# HV_power.net
KiCad netlist of a schematic drawn in Altium Designer
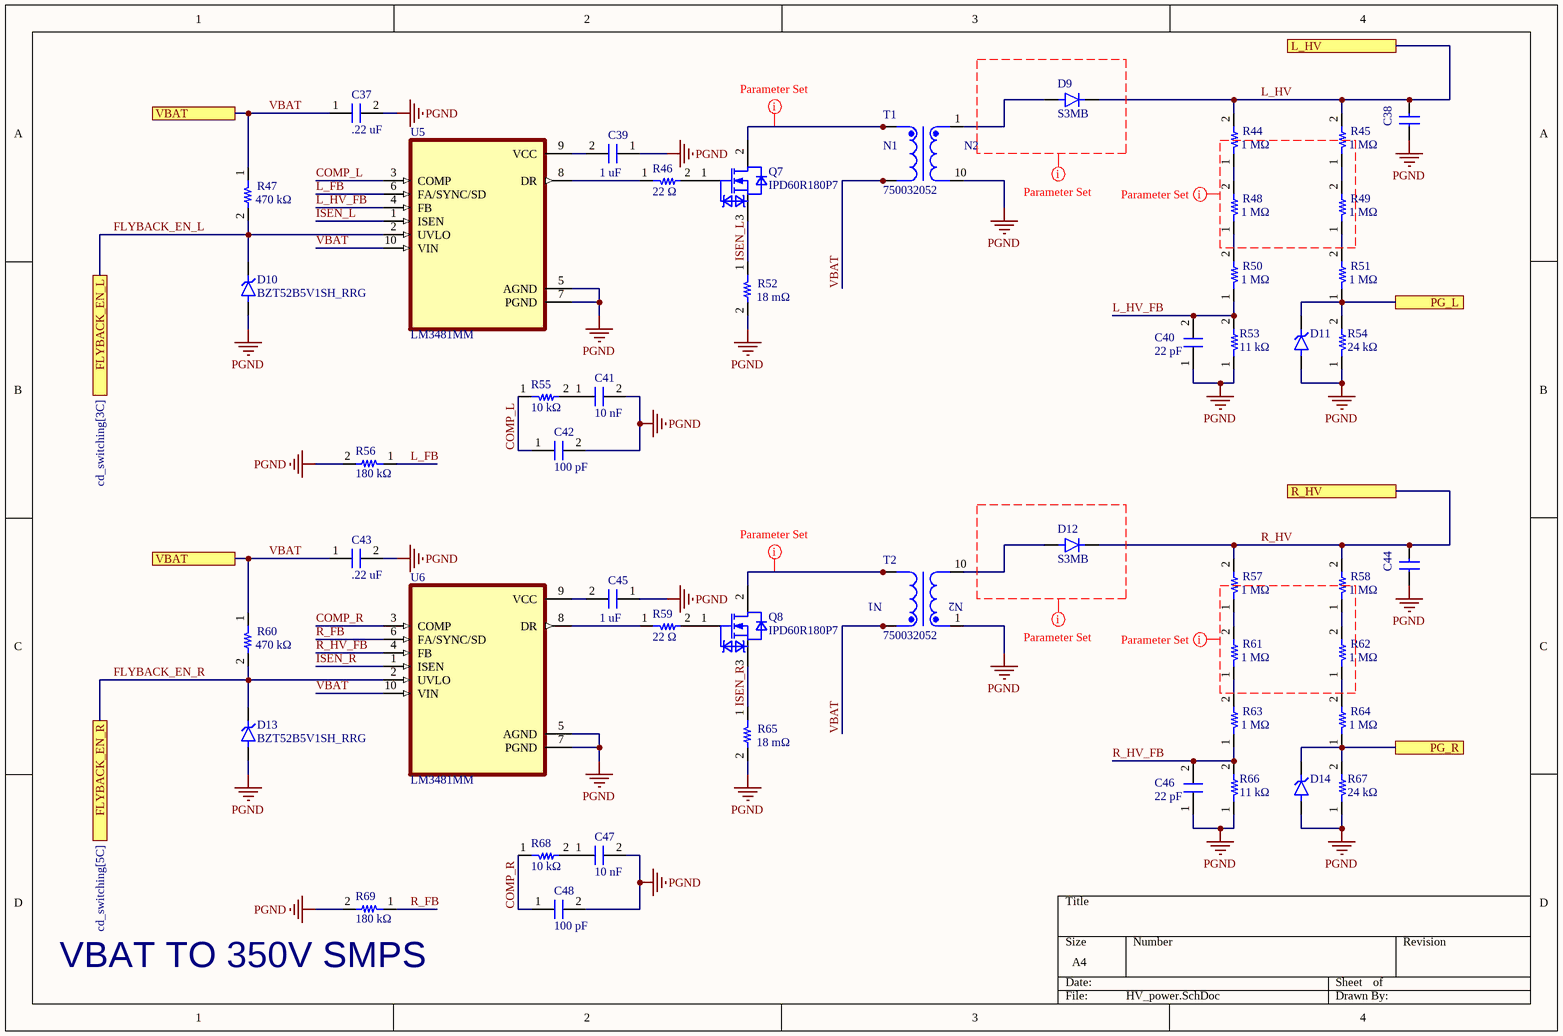
[diagram p0: HV_power.SchDoc]

(export (version "E")
  (design (tool "Eeschema 10.0.6"))
  (components
    (comp (ref "C37")
      (value ".22 uF")
      (footprint "0603_FP")
      (fields (field (name "Comment") "GRM21BR61C475KA88L"))
      (libsource (lib "RC_sch") (part "Capacitor_0603"))
    )
    (comp (ref "C38")
      (value "WCAP-FTBP_P10")
      (footprint "WCAP-FTBP_10X13X5.5X11(PXLXWXH)")
      (fields (field (name "MF") "Wurth Elektronik") (field (name "MP") "890283323005CS"))
      (libsource (lib "WCAP-FTBP_P10") (part "WCAP-FTBP_P10"))
    )
    (comp (ref "C39")
      (value "1 uF")
      (footprint "0603_FP")
      (fields (field (name "Comment") "Capacitor_0603"))
      (libsource (lib "RC_sch") (part "Capacitor_0603"))
    )
    (comp (ref "C40")
      (value "22 pF")
      (footprint "0603_FP")
      (fields (field (name "Comment") "Capacitor_0603"))
      (libsource (lib "RC_sch") (part "Capacitor_0603"))
    )
    (comp (ref "C41")
      (value "10 nF")
      (footprint "0603_FP")
      (fields (field (name "Comment") "Capacitor_0603"))
      (libsource (lib "RC_sch") (part "Capacitor_0603"))
    )
    (comp (ref "C42")
      (value "100 pF")
      (footprint "0603_FP")
      (fields (field (name "Comment") "Capacitor_0603"))
      (libsource (lib "RC_sch") (part "Capacitor_0603"))
    )
    (comp (ref "C43")
      (value ".22 uF")
      (footprint "0603_FP")
      (fields (field (name "Comment") "GRM21BR61C475KA88L"))
      (libsource (lib "RC_sch") (part "Capacitor_0603"))
    )
    (comp (ref "C44")
      (value "WCAP-FTBP_P10")
      (footprint "WCAP-FTBP_10X13X5.5X11(PXLXWXH)")
      (fields (field (name "MF") "Wurth Elektronik") (field (name "MP") "890283323005CS"))
      (libsource (lib "WCAP-FTBP_P10") (part "WCAP-FTBP_P10"))
    )
    (comp (ref "C45")
      (value "1 uF")
      (footprint "0603_FP")
      (fields (field (name "Comment") "Capacitor_0603"))
      (libsource (lib "RC_sch") (part "Capacitor_0603"))
    )
    (comp (ref "C46")
      (value "22 pF")
      (footprint "0603_FP")
      (fields (field (name "Comment") "Capacitor_0603"))
      (libsource (lib "RC_sch") (part "Capacitor_0603"))
    )
    (comp (ref "C47")
      (value "10 nF")
      (footprint "0603_FP")
      (fields (field (name "Comment") "Capacitor_0603"))
      (libsource (lib "RC_sch") (part "Capacitor_0603"))
    )
    (comp (ref "C48")
      (value "100 pF")
      (footprint "0603_FP")
      (fields (field (name "Comment") "Capacitor_0603"))
      (libsource (lib "RC_sch") (part "Capacitor_0603"))
    )
    (comp (ref "D9")
      (value "S3MB")
      (footprint "DIOM4336X265N")
      (description "3A, 1000V, Standard Recovery Rectifier")
      (fields (field (name "MF") "Taiwan Semiconductor"))
      (libsource (lib "S3MB") (part "S3MB"))
    )
    (comp (ref "D10")
      (value "BZT52B5V1SH_RRG")
      (footprint "DIO_BZT52B5V1SH_RRG")
      (description "SOD-323, 200mW, 2%, 5.1V, Zener Diode")
      (fields (field (name "MF") "Taiwan Semiconductor Corporation") (field (name "MP") "BZT52B5V1SH RRG"))
      (libsource (lib "BZT52B5V1SH_RRG") (part "BZT52B5V1SH_RRG"))
    )
    (comp (ref "D11")
      (value "BZT52B15SH_RRG")
      (footprint "DIO_BZT52B15SH_RRG")
      (description "SOD-323, 200mW, 2%, 15V, Zener Diode")
      (fields (field (name "MF") "Taiwan Semiconductor Corporation") (field (name "MP") "BZT52B15SH RRG"))
      (libsource (lib "BZT52B15SH_RRG") (part "BZT52B15SH_RRG"))
    )
    (comp (ref "D12")
      (value "S3MB")
      (footprint "DIOM4336X265N")
      (description "3A, 1000V, Standard Recovery Rectifier")
      (fields (field (name "MF") "Taiwan Semiconductor"))
      (libsource (lib "S3MB") (part "S3MB"))
    )
    (comp (ref "D13")
      (value "BZT52B5V1SH_RRG")
      (footprint "DIO_BZT52B5V1SH_RRG")
      (description "SOD-323, 200mW, 2%, 5.1V, Zener Diode")
      (fields (field (name "MF") "Taiwan Semiconductor Corporation") (field (name "MP") "BZT52B5V1SH RRG"))
      (libsource (lib "BZT52B5V1SH_RRG") (part "BZT52B5V1SH_RRG"))
    )
    (comp (ref "D14")
      (value "BZT52B15SH_RRG")
      (footprint "DIO_BZT52B15SH_RRG")
      (description "SOD-323, 200mW, 2%, 15V, Zener Diode")
      (fields (field (name "MF") "Taiwan Semiconductor Corporation") (field (name "MP") "BZT52B15SH RRG"))
      (libsource (lib "BZT52B15SH_RRG") (part "BZT52B15SH_RRG"))
    )
    (comp (ref "Q7")
      (value "IPD60R180P7")
      (footprint "DPAK228P987X240-3N")
      (fields (field (name "MANUFACTURER") "Infineon Technologies"))
      (libsource (lib "IPD60R180P7") (part "IPD60R180P7"))
    )
    (comp (ref "Q8")
      (value "IPD60R180P7")
      (footprint "DPAK228P987X240-3N")
      (fields (field (name "MANUFACTURER") "Infineon Technologies"))
      (libsource (lib "IPD60R180P7") (part "IPD60R180P7"))
    )
    (comp (ref "R44")
      (value "1 MΩ")
      (footprint "0805_FP")
      (fields (field (name "Comment") "R_0805"))
      (libsource (lib "0805_R") (part "R_0805"))
    )
    (comp (ref "R45")
      (value "1 MΩ")
      (footprint "0805_FP")
      (fields (field (name "Comment") "R_0805"))
      (libsource (lib "0805_R") (part "R_0805"))
    )
    (comp (ref "R46")
      (value "22 Ω")
      (footprint "0603_FP")
      (fields (field (name "Comment") "Resistor_0603"))
      (libsource (lib "RC_sch") (part "Resistor_0603"))
    )
    (comp (ref "R47")
      (value "470 kΩ")
      (footprint "0603_FP")
      (fields (field (name "Comment") "Resistor_0603"))
      (libsource (lib "RC_sch") (part "Resistor_0603"))
    )
    (comp (ref "R48")
      (value "1 MΩ")
      (footprint "0805_FP")
      (fields (field (name "Comment") "R_0805"))
      (libsource (lib "0805_R") (part "R_0805"))
    )
    (comp (ref "R49")
      (value "1 MΩ")
      (footprint "0805_FP")
      (fields (field (name "Comment") "R_0805"))
      (libsource (lib "0805_R") (part "R_0805"))
    )
    (comp (ref "R50")
      (value "1 MΩ")
      (footprint "0805_FP")
      (fields (field (name "Comment") "R_0805"))
      (libsource (lib "0805_R") (part "R_0805"))
    )
    (comp (ref "R51")
      (value "1 MΩ")
      (footprint "0805_FP")
      (fields (field (name "Comment") "R_0805"))
      (libsource (lib "0805_R") (part "R_0805"))
    )
    (comp (ref "R52")
      (value "18 mΩ")
      (footprint "2010_FP")
      (fields (field (name "Comment") "2010_res"))
      (libsource (lib "2010_R") (part "2010_res"))
    )
    (comp (ref "R53")
      (value "11 kΩ")
      (footprint "0805_FP")
      (fields (field (name "Comment") "R_0805"))
      (libsource (lib "0805_R") (part "R_0805"))
    )
    (comp (ref "R54")
      (value "24 kΩ")
      (footprint "0805_FP")
      (fields (field (name "Comment") "R_0805"))
      (libsource (lib "0805_R") (part "R_0805"))
    )
    (comp (ref "R55")
      (value "10 kΩ")
      (footprint "0603_FP")
      (fields (field (name "Comment") "Resistor_0603"))
      (libsource (lib "RC_sch") (part "Resistor_0603"))
    )
    (comp (ref "R56")
      (value "180 kΩ")
      (footprint "0603_FP")
      (fields (field (name "Comment") "Resistor_0603"))
      (libsource (lib "RC_sch") (part "Resistor_0603"))
    )
    (comp (ref "R57")
      (value "1 MΩ")
      (footprint "0805_FP")
      (fields (field (name "Comment") "R_0805"))
      (libsource (lib "0805_R") (part "R_0805"))
    )
    (comp (ref "R58")
      (value "1 MΩ")
      (footprint "0805_FP")
      (fields (field (name "Comment") "R_0805"))
      (libsource (lib "0805_R") (part "R_0805"))
    )
    (comp (ref "R59")
      (value "22 Ω")
      (footprint "0603_FP")
      (fields (field (name "Comment") "Resistor_0603"))
      (libsource (lib "RC_sch") (part "Resistor_0603"))
    )
    (comp (ref "R60")
      (value "470 kΩ")
      (footprint "0603_FP")
      (fields (field (name "Comment") "Resistor_0603"))
      (libsource (lib "RC_sch") (part "Resistor_0603"))
    )
    (comp (ref "R61")
      (value "1 MΩ")
      (footprint "0805_FP")
      (fields (field (name "Comment") "R_0805"))
      (libsource (lib "0805_R") (part "R_0805"))
    )
    (comp (ref "R62")
      (value "1 MΩ")
      (footprint "0805_FP")
      (fields (field (name "Comment") "R_0805"))
      (libsource (lib "0805_R") (part "R_0805"))
    )
    (comp (ref "R63")
      (value "1 MΩ")
      (footprint "0805_FP")
      (fields (field (name "Comment") "R_0805"))
      (libsource (lib "0805_R") (part "R_0805"))
    )
    (comp (ref "R64")
      (value "1 MΩ")
      (footprint "0805_FP")
      (fields (field (name "Comment") "R_0805"))
      (libsource (lib "0805_R") (part "R_0805"))
    )
    (comp (ref "R65")
      (value "18 mΩ")
      (footprint "2010_FP")
      (fields (field (name "Comment") "2010_res"))
      (libsource (lib "2010_R") (part "2010_res"))
    )
    (comp (ref "R66")
      (value "11 kΩ")
      (footprint "0805_FP")
      (fields (field (name "Comment") "R_0805"))
      (libsource (lib "0805_R") (part "R_0805"))
    )
    (comp (ref "R67")
      (value "24 kΩ")
      (footprint "0805_FP")
      (fields (field (name "Comment") "R_0805"))
      (libsource (lib "0805_R") (part "R_0805"))
    )
    (comp (ref "R68")
      (value "10 kΩ")
      (footprint "0603_FP")
      (fields (field (name "Comment") "Resistor_0603"))
      (libsource (lib "RC_sch") (part "Resistor_0603"))
    )
    (comp (ref "R69")
      (value "180 kΩ")
      (footprint "0603_FP")
      (fields (field (name "Comment") "Resistor_0603"))
      (libsource (lib "RC_sch") (part "Resistor_0603"))
    )
    (comp (ref "T1")
      (value "750032052")
      (footprint "WE-FB3751_EFD20")
      (fields (field (name "MF") "Wurth Electronics"))
      (libsource (lib "750032052") (part "750032052"))
    )
    (comp (ref "T2")
      (value "750032052")
      (footprint "WE-FB3751_EFD20")
      (fields (field (name "MF") "Wurth Electronics"))
      (libsource (lib "") (part "750032052_1"))
    )
    (comp (ref "U5")
      (value "LM3481MM")
      (footprint "SOP50P490X110-10N")
      (description "2.97V to 48V High-Efficiency Controller for Boost, SEPIC and Flyback")
      (fields (field (name "MF") "Texas Instruments") (field (name "MP") "LM3481MM/NOPB"))
      (libsource (lib "LM3481MM") (part "LM3481MM"))
    )
    (comp (ref "U6")
      (value "LM3481MM")
      (footprint "SOP50P490X110-10N")
      (description "2.97V to 48V High-Efficiency Controller for Boost, SEPIC and Flyback")
      (fields (field (name "MF") "Texas Instruments") (field (name "MP") "LM3481MM/NOPB"))
      (libsource (lib "LM3481MM") (part "LM3481MM"))
    )
  )
  (nets
    (net (code "1") (name "/COMP_L") (class "Default")
      (node (ref "C42") (pin "1") (pinfunction "1_1") (pintype "passive"))
      (node (ref "R55") (pin "1") (pinfunction "1_1") (pintype "passive"))
      (node (ref "U5") (pin "3") (pinfunction "COMP_3") (pintype "input"))
    )
    (net (code "2") (name "/COMP_R") (class "Default")
      (node (ref "C48") (pin "1") (pinfunction "1_1") (pintype "passive"))
      (node (ref "R68") (pin "1") (pinfunction "1_1") (pintype "passive"))
      (node (ref "U6") (pin "3") (pinfunction "COMP_3") (pintype "input"))
    )
    (net (code "3") (name "/FLYBACK_EN_L") (class "Default")
      (node (ref "D10") (pin "1") (pinfunction "K_1") (pintype "passive"))
      (node (ref "R47") (pin "2") (pinfunction "2_2") (pintype "passive"))
      (node (ref "U5") (pin "2") (pinfunction "UVLO_2") (pintype "input"))
    )
    (net (code "4") (name "/FLYBACK_EN_R") (class "Default")
      (node (ref "D13") (pin "1") (pinfunction "K_1") (pintype "passive"))
      (node (ref "R60") (pin "2") (pinfunction "2_2") (pintype "passive"))
      (node (ref "U6") (pin "2") (pinfunction "UVLO_2") (pintype "input"))
    )
    (net (code "5") (name "/ISEN_L") (class "Default")
      (node (ref "Q7") (pin "3") (pinfunction "SOURCE_3") (pintype "passive"))
      (node (ref "R52") (pin "1") (pinfunction "1_1") (pintype "passive"))
      (node (ref "U5") (pin "1") (pinfunction "ISEN_1") (pintype "input"))
    )
    (net (code "6") (name "/ISEN_R") (class "Default")
      (node (ref "Q8") (pin "3") (pinfunction "SOURCE_3") (pintype "passive"))
      (node (ref "R65") (pin "1") (pinfunction "1_1") (pintype "passive"))
      (node (ref "U6") (pin "1") (pinfunction "ISEN_1") (pintype "input"))
    )
    (net (code "7") (name "/L_FB") (class "Default")
      (node (ref "R56") (pin "1") (pinfunction "1_1") (pintype "passive"))
      (node (ref "U5") (pin "6") (pinfunction "FA/SYNC/SD_6") (pintype "input"))
    )
    (net (code "8") (name "/L_HV") (class "Default")
      (node (ref "C38") (pin "2") (pinfunction "2_2") (pintype "passive"))
      (node (ref "D9") (pin "C") (pinfunction "K_C") (pintype "passive"))
      (node (ref "R44") (pin "2") (pinfunction "2_2") (pintype "passive"))
      (node (ref "R45") (pin "2") (pinfunction "2_2") (pintype "passive"))
    )
    (net (code "9") (name "/L_HV_FB") (class "Default")
      (node (ref "C40") (pin "2") (pinfunction "2_2") (pintype "passive"))
      (node (ref "R50") (pin "1") (pinfunction "1_1") (pintype "passive"))
      (node (ref "R53") (pin "2") (pinfunction "2_2") (pintype "passive"))
      (node (ref "U5") (pin "4") (pinfunction "FB_4") (pintype "input"))
    )
    (net (code "10") (name "/PG_L") (class "Default")
      (node (ref "D11") (pin "1") (pinfunction "K_1") (pintype "passive"))
      (node (ref "R51") (pin "1") (pinfunction "1_1") (pintype "passive"))
      (node (ref "R54") (pin "2") (pinfunction "2_2") (pintype "passive"))
    )
    (net (code "11") (name "/PG_R") (class "Default")
      (node (ref "D14") (pin "1") (pinfunction "K_1") (pintype "passive"))
      (node (ref "R64") (pin "1") (pinfunction "1_1") (pintype "passive"))
      (node (ref "R67") (pin "2") (pinfunction "2_2") (pintype "passive"))
    )
    (net (code "12") (name "/R_FB") (class "Default")
      (node (ref "R69") (pin "1") (pinfunction "1_1") (pintype "passive"))
      (node (ref "U6") (pin "6") (pinfunction "FA/SYNC/SD_6") (pintype "input"))
    )
    (net (code "13") (name "/R_HV") (class "Default")
      (node (ref "C44") (pin "2") (pinfunction "2_2") (pintype "passive"))
      (node (ref "D12") (pin "C") (pinfunction "K_C") (pintype "passive"))
      (node (ref "R57") (pin "2") (pinfunction "2_2") (pintype "passive"))
      (node (ref "R58") (pin "2") (pinfunction "2_2") (pintype "passive"))
    )
    (net (code "14") (name "/R_HV_FB") (class "Default")
      (node (ref "C46") (pin "2") (pinfunction "2_2") (pintype "passive"))
      (node (ref "R63") (pin "1") (pinfunction "1_1") (pintype "passive"))
      (node (ref "R66") (pin "2") (pinfunction "2_2") (pintype "passive"))
      (node (ref "U6") (pin "4") (pinfunction "FB_4") (pintype "input"))
    )
    (net (code "15") (name "/VBAT") (class "Default")
      (node (ref "C37") (pin "1") (pinfunction "1_1") (pintype "passive"))
      (node (ref "C43") (pin "1") (pinfunction "1_1") (pintype "passive"))
      (node (ref "R47") (pin "1") (pinfunction "1_1") (pintype "passive"))
      (node (ref "R60") (pin "1") (pinfunction "1_1") (pintype "passive"))
      (node (ref "T1") (pin "4") (pinfunction "4+5_4") (pintype "passive"))
      (node (ref "T1") (pin "5") (pinfunction "4+5_5") (pintype "passive"))
      (node (ref "T2") (pin "6") (pinfunction "6+7_6") (pintype "passive"))
      (node (ref "T2") (pin "7") (pinfunction "6+7_7") (pintype "passive"))
      (node (ref "U5") (pin "10") (pinfunction "VIN_10") (pintype "input"))
      (node (ref "U6") (pin "10") (pinfunction "VIN_10") (pintype "input"))
    )
    (net (code "16") (name "Net-(C41-Pad1)") (class "Default")
      (node (ref "C41") (pin "1") (pinfunction "1_1") (pintype "passive"))
      (node (ref "R55") (pin "2") (pinfunction "2_2") (pintype "passive"))
    )
    (net (code "17") (name "Net-(C47-Pad1)") (class "Default")
      (node (ref "C47") (pin "1") (pinfunction "1_1") (pintype "passive"))
      (node (ref "R68") (pin "2") (pinfunction "2_2") (pintype "passive"))
    )
    (net (code "18") (name "Net-(D9-PadA)") (class "Default")
      (node (ref "D9") (pin "A") (pinfunction "A_A") (pintype "passive"))
      (node (ref "T1") (pin "1") (pinfunction "1_1") (pintype "passive"))
    )
    (net (code "19") (name "Net-(D12-PadA)") (class "Default")
      (node (ref "D12") (pin "A") (pinfunction "A_A") (pintype "passive"))
      (node (ref "T2") (pin "10") (pinfunction "10_10") (pintype "passive"))
    )
    (net (code "20") (name "Net-(Q7-DRAIN)") (class "Default")
      (node (ref "Q7") (pin "2") (pinfunction "DRAIN_2") (pintype "passive"))
      (node (ref "T1") (pin "6") (pinfunction "6+7_6") (pintype "passive"))
      (node (ref "T1") (pin "7") (pinfunction "6+7_7") (pintype "passive"))
    )
    (net (code "21") (name "Net-(Q7-GATE)") (class "Default")
      (node (ref "Q7") (pin "1") (pinfunction "GATE_1") (pintype "passive"))
      (node (ref "R46") (pin "2") (pinfunction "2_2") (pintype "passive"))
    )
    (net (code "22") (name "Net-(Q8-DRAIN)") (class "Default")
      (node (ref "Q8") (pin "2") (pinfunction "DRAIN_2") (pintype "passive"))
      (node (ref "T2") (pin "4") (pinfunction "4+5_4") (pintype "passive"))
      (node (ref "T2") (pin "5") (pinfunction "4+5_5") (pintype "passive"))
    )
    (net (code "23") (name "Net-(Q8-GATE)") (class "Default")
      (node (ref "Q8") (pin "1") (pinfunction "GATE_1") (pintype "passive"))
      (node (ref "R59") (pin "2") (pinfunction "2_2") (pintype "passive"))
    )
    (net (code "24") (name "Net-(R44-Pad1)") (class "Default")
      (node (ref "R44") (pin "1") (pinfunction "1_1") (pintype "passive"))
      (node (ref "R48") (pin "2") (pinfunction "2_2") (pintype "passive"))
    )
    (net (code "25") (name "Net-(R45-Pad1)") (class "Default")
      (node (ref "R45") (pin "1") (pinfunction "1_1") (pintype "passive"))
      (node (ref "R49") (pin "2") (pinfunction "2_2") (pintype "passive"))
    )
    (net (code "26") (name "Net-(R48-Pad1)") (class "Default")
      (node (ref "R48") (pin "1") (pinfunction "1_1") (pintype "passive"))
      (node (ref "R50") (pin "2") (pinfunction "2_2") (pintype "passive"))
    )
    (net (code "27") (name "Net-(R49-Pad1)") (class "Default")
      (node (ref "R49") (pin "1") (pinfunction "1_1") (pintype "passive"))
      (node (ref "R51") (pin "2") (pinfunction "2_2") (pintype "passive"))
    )
    (net (code "28") (name "Net-(R57-Pad1)") (class "Default")
      (node (ref "R57") (pin "1") (pinfunction "1_1") (pintype "passive"))
      (node (ref "R61") (pin "2") (pinfunction "2_2") (pintype "passive"))
    )
    (net (code "29") (name "Net-(R58-Pad1)") (class "Default")
      (node (ref "R58") (pin "1") (pinfunction "1_1") (pintype "passive"))
      (node (ref "R62") (pin "2") (pinfunction "2_2") (pintype "passive"))
    )
    (net (code "30") (name "Net-(R61-Pad1)") (class "Default")
      (node (ref "R61") (pin "1") (pinfunction "1_1") (pintype "passive"))
      (node (ref "R63") (pin "2") (pinfunction "2_2") (pintype "passive"))
    )
    (net (code "31") (name "Net-(R62-Pad1)") (class "Default")
      (node (ref "R62") (pin "1") (pinfunction "1_1") (pintype "passive"))
      (node (ref "R64") (pin "2") (pinfunction "2_2") (pintype "passive"))
    )
    (net (code "32") (name "Net-(U5-DR)") (class "Default")
      (node (ref "R46") (pin "1") (pinfunction "1_1") (pintype "passive"))
      (node (ref "U5") (pin "8") (pinfunction "DR_8") (pintype "output"))
    )
    (net (code "33") (name "Net-(U5-VCC)") (class "Default")
      (node (ref "C39") (pin "2") (pinfunction "2_2") (pintype "passive"))
      (node (ref "U5") (pin "9") (pinfunction "VCC_9") (pintype "power_in"))
    )
    (net (code "34") (name "Net-(U6-DR)") (class "Default")
      (node (ref "R59") (pin "1") (pinfunction "1_1") (pintype "passive"))
      (node (ref "U6") (pin "8") (pinfunction "DR_8") (pintype "output"))
    )
    (net (code "35") (name "Net-(U6-VCC)") (class "Default")
      (node (ref "C45") (pin "2") (pinfunction "2_2") (pintype "passive"))
      (node (ref "U6") (pin "9") (pinfunction "VCC_9") (pintype "power_in"))
    )
    (net (code "36") (name "PGND") (class "Default")
      (node (ref "C37") (pin "2") (pinfunction "2_2") (pintype "passive"))
      (node (ref "C38") (pin "1") (pinfunction "1_1") (pintype "passive"))
      (node (ref "C39") (pin "1") (pinfunction "1_1") (pintype "passive"))
      (node (ref "C40") (pin "1") (pinfunction "1_1") (pintype "passive"))
      (node (ref "C41") (pin "2") (pinfunction "2_2") (pintype "passive"))
      (node (ref "C42") (pin "2") (pinfunction "2_2") (pintype "passive"))
      (node (ref "C43") (pin "2") (pinfunction "2_2") (pintype "passive"))
      (node (ref "C44") (pin "1") (pinfunction "1_1") (pintype "passive"))
      (node (ref "C45") (pin "1") (pinfunction "1_1") (pintype "passive"))
      (node (ref "C46") (pin "1") (pinfunction "1_1") (pintype "passive"))
      (node (ref "C47") (pin "2") (pinfunction "2_2") (pintype "passive"))
      (node (ref "C48") (pin "2") (pinfunction "2_2") (pintype "passive"))
      (node (ref "D10") (pin "2") (pinfunction "A_2") (pintype "passive"))
      (node (ref "D11") (pin "2") (pinfunction "A_2") (pintype "passive"))
      (node (ref "D13") (pin "2") (pinfunction "A_2") (pintype "passive"))
      (node (ref "D14") (pin "2") (pinfunction "A_2") (pintype "passive"))
      (node (ref "R52") (pin "2") (pinfunction "2_2") (pintype "passive"))
      (node (ref "R53") (pin "1") (pinfunction "1_1") (pintype "passive"))
      (node (ref "R54") (pin "1") (pinfunction "1_1") (pintype "passive"))
      (node (ref "R56") (pin "2") (pinfunction "2_2") (pintype "passive"))
      (node (ref "R65") (pin "2") (pinfunction "2_2") (pintype "passive"))
      (node (ref "R66") (pin "1") (pinfunction "1_1") (pintype "passive"))
      (node (ref "R67") (pin "1") (pinfunction "1_1") (pintype "passive"))
      (node (ref "R69") (pin "2") (pinfunction "2_2") (pintype "passive"))
      (node (ref "T1") (pin "10") (pinfunction "10_10") (pintype "passive"))
      (node (ref "T2") (pin "1") (pinfunction "1_1") (pintype "passive"))
      (node (ref "U5") (pin "5") (pinfunction "AGND_5") (pintype "power_in"))
      (node (ref "U5") (pin "7") (pinfunction "PGND_7") (pintype "power_in"))
      (node (ref "U6") (pin "5") (pinfunction "AGND_5") (pintype "power_in"))
      (node (ref "U6") (pin "7") (pinfunction "PGND_7") (pintype "power_in"))
    )
  )
)
